# CCD_3.net
KiCad netlist of a schematic drawn in Altium Designer
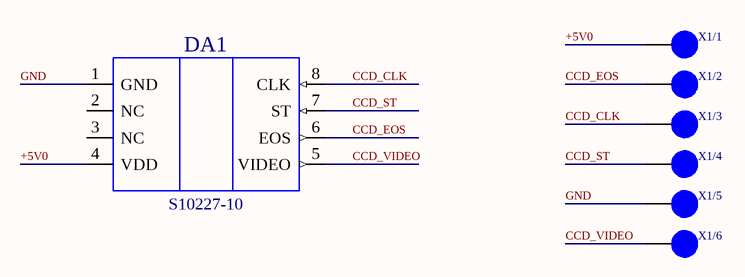
[diagram p0: Плата CCD Э3.SchDoc]

(export (version "E")
  (design (tool "Eeschema 10.0.6"))
  (components
    (comp (ref "DA1")
      (value "S10227-10")
      (footprint "S10227-10")
      (description "Микросхема S10227-10")
      (libsource (lib "Плата излучателя") (part "S10227-10"))
    )
    (comp (ref "X1/1")
      (value "SolderPint")
      (footprint "PCB_PAD")
      (libsource (lib "АРМ.24.07") (part "SolderPoint"))
    )
    (comp (ref "X1/2")
      (value "SolderPint")
      (footprint "PCB_PAD")
      (libsource (lib "АРМ.24.07") (part "SolderPoint"))
    )
    (comp (ref "X1/3")
      (value "SolderPint")
      (footprint "PCB_PAD")
      (libsource (lib "АРМ.24.07") (part "SolderPoint"))
    )
    (comp (ref "X1/4")
      (value "SolderPint")
      (footprint "PCB_PAD")
      (libsource (lib "АРМ.24.07") (part "SolderPoint"))
    )
    (comp (ref "X1/5")
      (value "SolderPint")
      (footprint "PCB_PAD")
      (libsource (lib "АРМ.24.07") (part "SolderPoint"))
    )
    (comp (ref "X1/6")
      (value "SolderPint")
      (footprint "PCB_PAD")
      (libsource (lib "АРМ.24.07") (part "SolderPoint"))
    )
  )
  (nets
    (net (code "1") (name "/+5V0") (class "Default")
      (node (ref "DA1") (pin "4") (pinfunction "VDD_4") (pintype "power_in"))
      (node (ref "X1/1") (pin "1") (pinfunction "1_1") (pintype "passive"))
    )
    (net (code "2") (name "/CCD_CLK") (class "Default")
      (node (ref "DA1") (pin "8") (pinfunction "CLK_8") (pintype "input"))
      (node (ref "X1/3") (pin "1") (pinfunction "1_1") (pintype "passive"))
    )
    (net (code "3") (name "/CCD_EOS") (class "Default")
      (node (ref "DA1") (pin "6") (pinfunction "EOS_6") (pintype "output"))
      (node (ref "X1/2") (pin "1") (pinfunction "1_1") (pintype "passive"))
    )
    (net (code "4") (name "/CCD_ST") (class "Default")
      (node (ref "DA1") (pin "7") (pinfunction "ST_7") (pintype "input"))
      (node (ref "X1/4") (pin "1") (pinfunction "1_1") (pintype "passive"))
    )
    (net (code "5") (name "/CCD_VIDEO") (class "Default")
      (node (ref "DA1") (pin "5") (pinfunction "VIDEO_5") (pintype "output"))
      (node (ref "X1/6") (pin "1") (pinfunction "1_1") (pintype "passive"))
    )
    (net (code "6") (name "/GND") (class "Default")
      (node (ref "DA1") (pin "1") (pinfunction "GND_1") (pintype "passive"))
      (node (ref "X1/5") (pin "1") (pinfunction "1_1") (pintype "passive"))
    )
    (net (code "7") (name "unconnected-(DA1-NC-Pad2)") (class "Default")
      (node (ref "DA1") (pin "2") (pinfunction "NC_2") (pintype "passive"))
    )
    (net (code "8") (name "unconnected-(DA1-NC-Pad3)") (class "Default")
      (node (ref "DA1") (pin "3") (pinfunction "NC_3") (pintype "passive"))
    )
  )
)
